# PowerSource.net
KiCad netlist of a schematic drawn in EAGLE
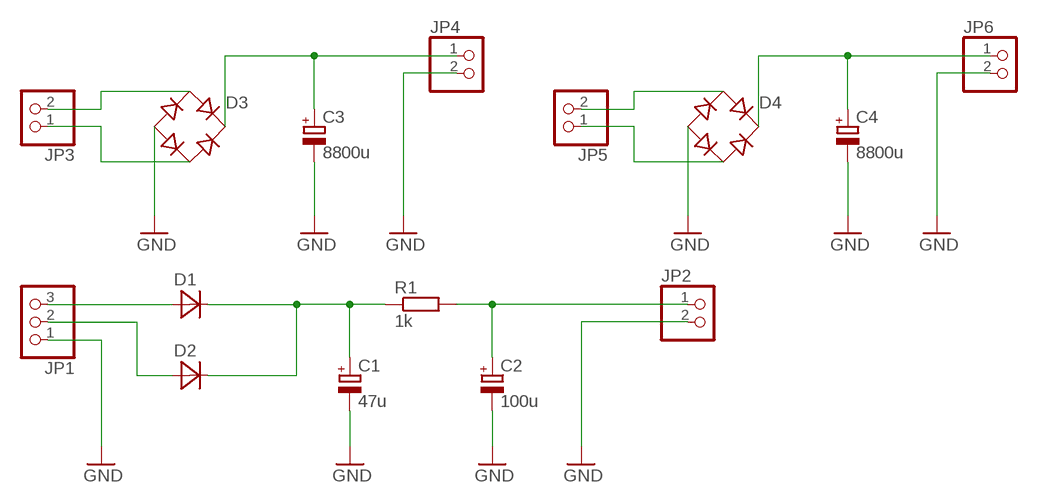
[diagram p0: schematic, sheet 1]

(export (version "E")
  (design (tool "Eeschema 10.0.6"))
  (components
    (comp (ref "C1")
      (value "47u")
      (footprint "eagle-import:E7,5-16")
      (libsource (lib "eagle-import") (part "E7.5-16"))
    )
    (comp (ref "C2")
      (value "100u")
      (footprint "eagle-import:E7,5-18")
      (libsource (lib "eagle-import") (part "E7.5-18"))
    )
    (comp (ref "C3")
      (value "8800u")
      (footprint "eagle-import:E7,5-18")
      (libsource (lib "eagle-import") (part "E7.5-18"))
    )
    (comp (ref "C4")
      (value "8800u")
      (footprint "eagle-import:E7,5-18")
      (libsource (lib "eagle-import") (part "E7.5-18"))
    )
    (comp (ref "D1")
      (value "DIODE")
      (footprint "eagle-import:DO07")
      (libsource (lib "eagle-import") (part "DIODE"))
    )
    (comp (ref "D2")
      (value "DIODE")
      (footprint "eagle-import:DO07")
      (libsource (lib "eagle-import") (part "DIODE"))
    )
    (comp (ref "D3")
      (value "BRIDGERECTIFIER")
      (footprint "eagle-import:BRIDGERECTIFIER")
      (libsource (lib "eagle-import") (part "BRIDGERECTIFIER"))
    )
    (comp (ref "D4")
      (value "BRIDGERECTIFIER")
      (footprint "eagle-import:BRIDGERECTIFIER")
      (libsource (lib "eagle-import") (part "BRIDGERECTIFIER"))
    )
    (comp (ref "JP1")
      (value "PINHD-1X3")
      (footprint "eagle-import:1X03")
      (libsource (lib "eagle-import") (part "PINHD-1X3"))
    )
    (comp (ref "JP2")
      (value "PINHD-1X2")
      (footprint "eagle-import:1X02")
      (libsource (lib "eagle-import") (part "PINHD-1X2"))
    )
    (comp (ref "JP3")
      (value "PINHD-1X2")
      (footprint "eagle-import:1X02")
      (libsource (lib "eagle-import") (part "PINHD-1X2"))
    )
    (comp (ref "JP4")
      (value "PINHD-1X2")
      (footprint "eagle-import:1X02")
      (libsource (lib "eagle-import") (part "PINHD-1X2"))
    )
    (comp (ref "JP5")
      (value "PINHD-1X2")
      (footprint "eagle-import:1X02")
      (libsource (lib "eagle-import") (part "PINHD-1X2"))
    )
    (comp (ref "JP6")
      (value "PINHD-1X2")
      (footprint "eagle-import:1X02")
      (libsource (lib "eagle-import") (part "PINHD-1X2"))
    )
    (comp (ref "R1")
      (value "1k")
      (footprint "eagle-import:0207_7")
      (libsource (lib "eagle-import") (part "RESISTOR2"))
    )
  )
  (nets
    (net (code "1") (name "GND") (class "Default")
      (node (ref "C1") (pin "-") (pinfunction "-_-") (pintype "passive"))
      (node (ref "C2") (pin "-") (pinfunction "-_-") (pintype "passive"))
      (node (ref "C3") (pin "-") (pinfunction "-_-") (pintype "passive"))
      (node (ref "C4") (pin "-") (pinfunction "-_-") (pintype "passive"))
      (node (ref "D3") (pin "-") (pinfunction "-_-") (pintype "passive"))
      (node (ref "D4") (pin "-") (pinfunction "-_-") (pintype "passive"))
      (node (ref "JP1") (pin "1") (pinfunction "1_1") (pintype "passive"))
      (node (ref "JP2") (pin "2") (pinfunction "2_2") (pintype "passive"))
      (node (ref "JP4") (pin "2") (pinfunction "2_2") (pintype "passive"))
      (node (ref "JP6") (pin "2") (pinfunction "2_2") (pintype "passive"))
    )
    (net (code "2") (name "Net-(C1-Pad+)") (class "Default")
      (node (ref "C1") (pin "+") (pinfunction "+_+") (pintype "passive"))
      (node (ref "D1") (pin "C") (pinfunction "C_C") (pintype "passive"))
      (node (ref "D2") (pin "C") (pinfunction "C_C") (pintype "passive"))
      (node (ref "R1") (pin "1") (pinfunction "1_1") (pintype "passive"))
    )
    (net (code "3") (name "Net-(C2-Pad+)") (class "Default")
      (node (ref "C2") (pin "+") (pinfunction "+_+") (pintype "passive"))
      (node (ref "JP2") (pin "1") (pinfunction "1_1") (pintype "passive"))
      (node (ref "R1") (pin "2") (pinfunction "2_2") (pintype "passive"))
    )
    (net (code "4") (name "Net-(C3-Pad+)") (class "Default")
      (node (ref "C3") (pin "+") (pinfunction "+_+") (pintype "passive"))
      (node (ref "D3") (pin "+") (pinfunction "+_+") (pintype "passive"))
      (node (ref "JP4") (pin "1") (pinfunction "1_1") (pintype "passive"))
    )
    (net (code "5") (name "Net-(C4-Pad+)") (class "Default")
      (node (ref "C4") (pin "+") (pinfunction "+_+") (pintype "passive"))
      (node (ref "D4") (pin "+") (pinfunction "+_+") (pintype "passive"))
      (node (ref "JP6") (pin "1") (pinfunction "1_1") (pintype "passive"))
    )
    (net (code "6") (name "Net-(D1-PadA)") (class "Default")
      (node (ref "D1") (pin "A") (pinfunction "A_A") (pintype "passive"))
      (node (ref "JP1") (pin "3") (pinfunction "3_3") (pintype "passive"))
    )
    (net (code "7") (name "Net-(D2-PadA)") (class "Default")
      (node (ref "D2") (pin "A") (pinfunction "A_A") (pintype "passive"))
      (node (ref "JP1") (pin "2") (pinfunction "2_2") (pintype "passive"))
    )
    (net (code "8") (name "Net-(D3-PadAC1)") (class "Default")
      (node (ref "D3") (pin "AC1") (pinfunction "AC1_AC1") (pintype "passive"))
      (node (ref "JP3") (pin "2") (pinfunction "2_2") (pintype "passive"))
    )
    (net (code "9") (name "Net-(D3-PadAC2)") (class "Default")
      (node (ref "D3") (pin "AC2") (pinfunction "AC2_AC2") (pintype "passive"))
      (node (ref "JP3") (pin "1") (pinfunction "1_1") (pintype "passive"))
    )
    (net (code "10") (name "Net-(D4-PadAC1)") (class "Default")
      (node (ref "D4") (pin "AC1") (pinfunction "AC1_AC1") (pintype "passive"))
      (node (ref "JP5") (pin "2") (pinfunction "2_2") (pintype "passive"))
    )
    (net (code "11") (name "Net-(D4-PadAC2)") (class "Default")
      (node (ref "D4") (pin "AC2") (pinfunction "AC2_AC2") (pintype "passive"))
      (node (ref "JP5") (pin "1") (pinfunction "1_1") (pintype "passive"))
    )
  )
)
